# 4_AV.net
KiCad netlist of a schematic drawn in Altium Designer
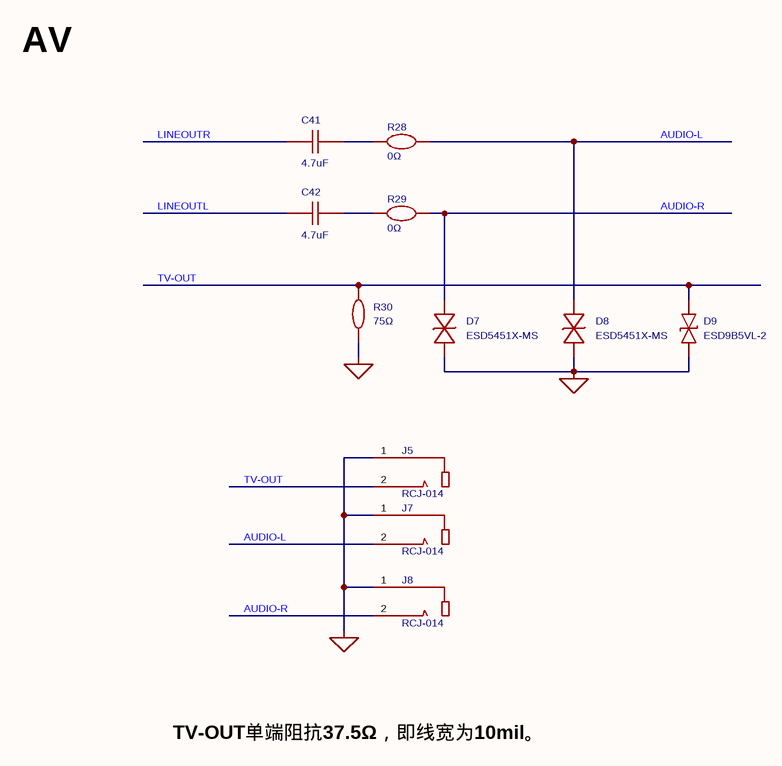
[diagram p0: 4_AV.schdoc]

(export (version "E")
  (design (tool "Eeschema 10.0.6"))
  (components
    (comp (ref "C41")
      (value "4.7uF")
      (footprint "C0402")
      (description "容值:4.7uF;精度:±20%;额定电压:25V;温度系数:-;")
      (fields
        (field (name "MANUFACTURER") "muRata(村田)")
        (field (name "MANUFACTURERPART") "GRM155C61E475ME15D")
      )
      (libsource (lib "altium-import") (part "root_0_GRM155C61E475ME15D_"))
    )
    (comp (ref "C42")
      (value "4.7uF")
      (footprint "C0402")
      (description "容值:4.7uF;精度:±20%;额定电压:25V;温度系数:-;")
      (fields
        (field (name "MANUFACTURER") "muRata(村田)")
        (field (name "MANUFACTURERPART") "GRM155C61E475ME15D")
      )
      (libsource (lib "altium-import") (part "root_0_GRM155C61E475ME15D_"))
    )
    (comp (ref "D7")
      (value "ESD5451X-MS")
      (footprint "DFN1006-2L-BI")
      (description "反向截止电压(Vrwm):5V;峰值脉冲电流(Ipp):8A;击穿电压:5.6V;")
      (fields (field (name "MANUFACTURER") "MSKSEMI(美森科)"))
      (libsource (lib "altium-import") (part "root_1_ESD5451X-MS_"))
    )
    (comp (ref "D8")
      (value "ESD5451X-MS")
      (footprint "DFN1006-2L-BI")
      (description "反向截止电压(Vrwm):5V;峰值脉冲电流(Ipp):8A;击穿电压:5.6V;")
      (fields (field (name "MANUFACTURER") "MSKSEMI(美森科)"))
      (libsource (lib "altium-import") (part "root_1_ESD5451X-MS_"))
    )
    (comp (ref "D9")
      (value "ESD9B5VL-2")
      (footprint "DFN1006-2L-BI")
      (description "反向截止电压(Vrwm):5V;钳位电压:12.5V;峰值脉冲功率(Ppp):80W@8/20us;击穿电压:6V;")
      (fields (field (name "MANUFACTURER") "Leiditech(雷卯电子)"))
      (libsource (lib "altium-import") (part "root_1_ESD9B5VL-2_"))
    )
    (comp (ref "J5")
      (value "RCJ-014")
      (footprint "CONN-TH_RCJ-013")
      (description "RCA插孔")
      (fields (field (name "MANUFACTURER") "CUI"))
      (libsource (lib "altium-import") (part "root_2_RCJ-014_"))
    )
    (comp (ref "J7")
      (value "RCJ-014")
      (footprint "CONN-TH_RCJ-013")
      (description "RCA插孔")
      (fields (field (name "MANUFACTURER") "CUI"))
      (libsource (lib "altium-import") (part "root_2_RCJ-014_"))
    )
    (comp (ref "J8")
      (value "RCJ-014")
      (footprint "CONN-TH_RCJ-013")
      (description "RCA插孔")
      (fields (field (name "MANUFACTURER") "CUI"))
      (libsource (lib "altium-import") (part "root_2_RCJ-014_"))
    )
    (comp (ref "R28")
      (value "0Ω")
      (footprint "R0402")
      (description "电阻类型:厚膜电阻;阻值:0Ω;精度:±5%;功率:62.5mW;工作电压:50V;")
      (fields (field (name "MANUFACTURER") "FOJAN(富捷)") (field (name "MANUFACTURERPART") "FRC0402P000 TS"))
      (libsource (lib "altium-import") (part "root_0_FRC0402P000 TS_"))
    )
    (comp (ref "R29")
      (value "0Ω")
      (footprint "R0402")
      (description "电阻类型:厚膜电阻;阻值:0Ω;精度:±5%;功率:62.5mW;工作电压:50V;")
      (fields (field (name "MANUFACTURER") "FOJAN(富捷)") (field (name "MANUFACTURERPART") "FRC0402P000 TS"))
      (libsource (lib "altium-import") (part "root_0_FRC0402P000 TS_"))
    )
    (comp (ref "R30")
      (value "75Ω")
      (footprint "R0603")
      (description "电阻类型:厚膜电阻;阻值:75Ω;精度:±1%;功率:100mW;工作电压:75V;温度系数:±100ppm/℃;")
      (fields
        (field (name "MANUFACTURER") "UNI-ROYAL(厚声)")
        (field (name "MANUFACTURER PART") "0603WAF750JT5E")
      )
      (libsource (lib "altium-import") (part "root_1_0603WAF750JT5E_"))
    )
  )
  (nets
    (net (code "2") (name "/AUDIO-L") (class "Default")
      (node (ref "D8") (pin "2") (pinfunction "2_2") (pintype "passive"))
      (node (ref "J7") (pin "2") (pinfunction "2_2") (pintype "passive"))
      (node (ref "R28") (pin "2") (pinfunction "2_2") (pintype "passive"))
    )
    (net (code "3") (name "/AUDIO-R") (class "Default")
      (node (ref "D7") (pin "2") (pinfunction "2_2") (pintype "passive"))
      (node (ref "J8") (pin "2") (pinfunction "2_2") (pintype "passive"))
      (node (ref "R29") (pin "2") (pinfunction "2_2") (pintype "passive"))
    )
    (net (code "4") (name "/LINEOUTL") (class "Default")
      (node (ref "C42") (pin "1") (pinfunction "1_1") (pintype "passive"))
    )
    (net (code "5") (name "/LINEOUTR") (class "Default")
      (node (ref "C41") (pin "1") (pinfunction "1_1") (pintype "passive"))
    )
    (net (code "6") (name "/TV-OUT") (class "Default")
      (node (ref "D9") (pin "2") (pinfunction "2_2") (pintype "passive"))
      (node (ref "J5") (pin "2") (pinfunction "2_2") (pintype "passive"))
      (node (ref "R30") (pin "2") (pinfunction "2_2") (pintype "passive"))
    )
    (net (code "7") (name "AGND") (class "Default")
      (node (ref "D7") (pin "1") (pinfunction "1_1") (pintype "passive"))
      (node (ref "D8") (pin "1") (pinfunction "1_1") (pintype "passive"))
      (node (ref "D9") (pin "1") (pinfunction "1_1") (pintype "passive"))
      (node (ref "J5") (pin "1") (pinfunction "1_1") (pintype "passive"))
      (node (ref "J7") (pin "1") (pinfunction "1_1") (pintype "passive"))
      (node (ref "J8") (pin "1") (pinfunction "1_1") (pintype "passive"))
      (node (ref "R30") (pin "1") (pinfunction "1_1") (pintype "passive"))
    )
    (net (code "8") (name "Net-(C41-Pad2)") (class "Default")
      (node (ref "C41") (pin "2") (pinfunction "2_2") (pintype "passive"))
      (node (ref "R28") (pin "1") (pinfunction "1_1") (pintype "passive"))
    )
    (net (code "9") (name "Net-(C42-Pad2)") (class "Default")
      (node (ref "C42") (pin "2") (pinfunction "2_2") (pintype "passive"))
      (node (ref "R29") (pin "1") (pinfunction "1_1") (pintype "passive"))
    )
  )
)
